# module_wifi.net
KiCad netlist of a schematic drawn in Altium Designer
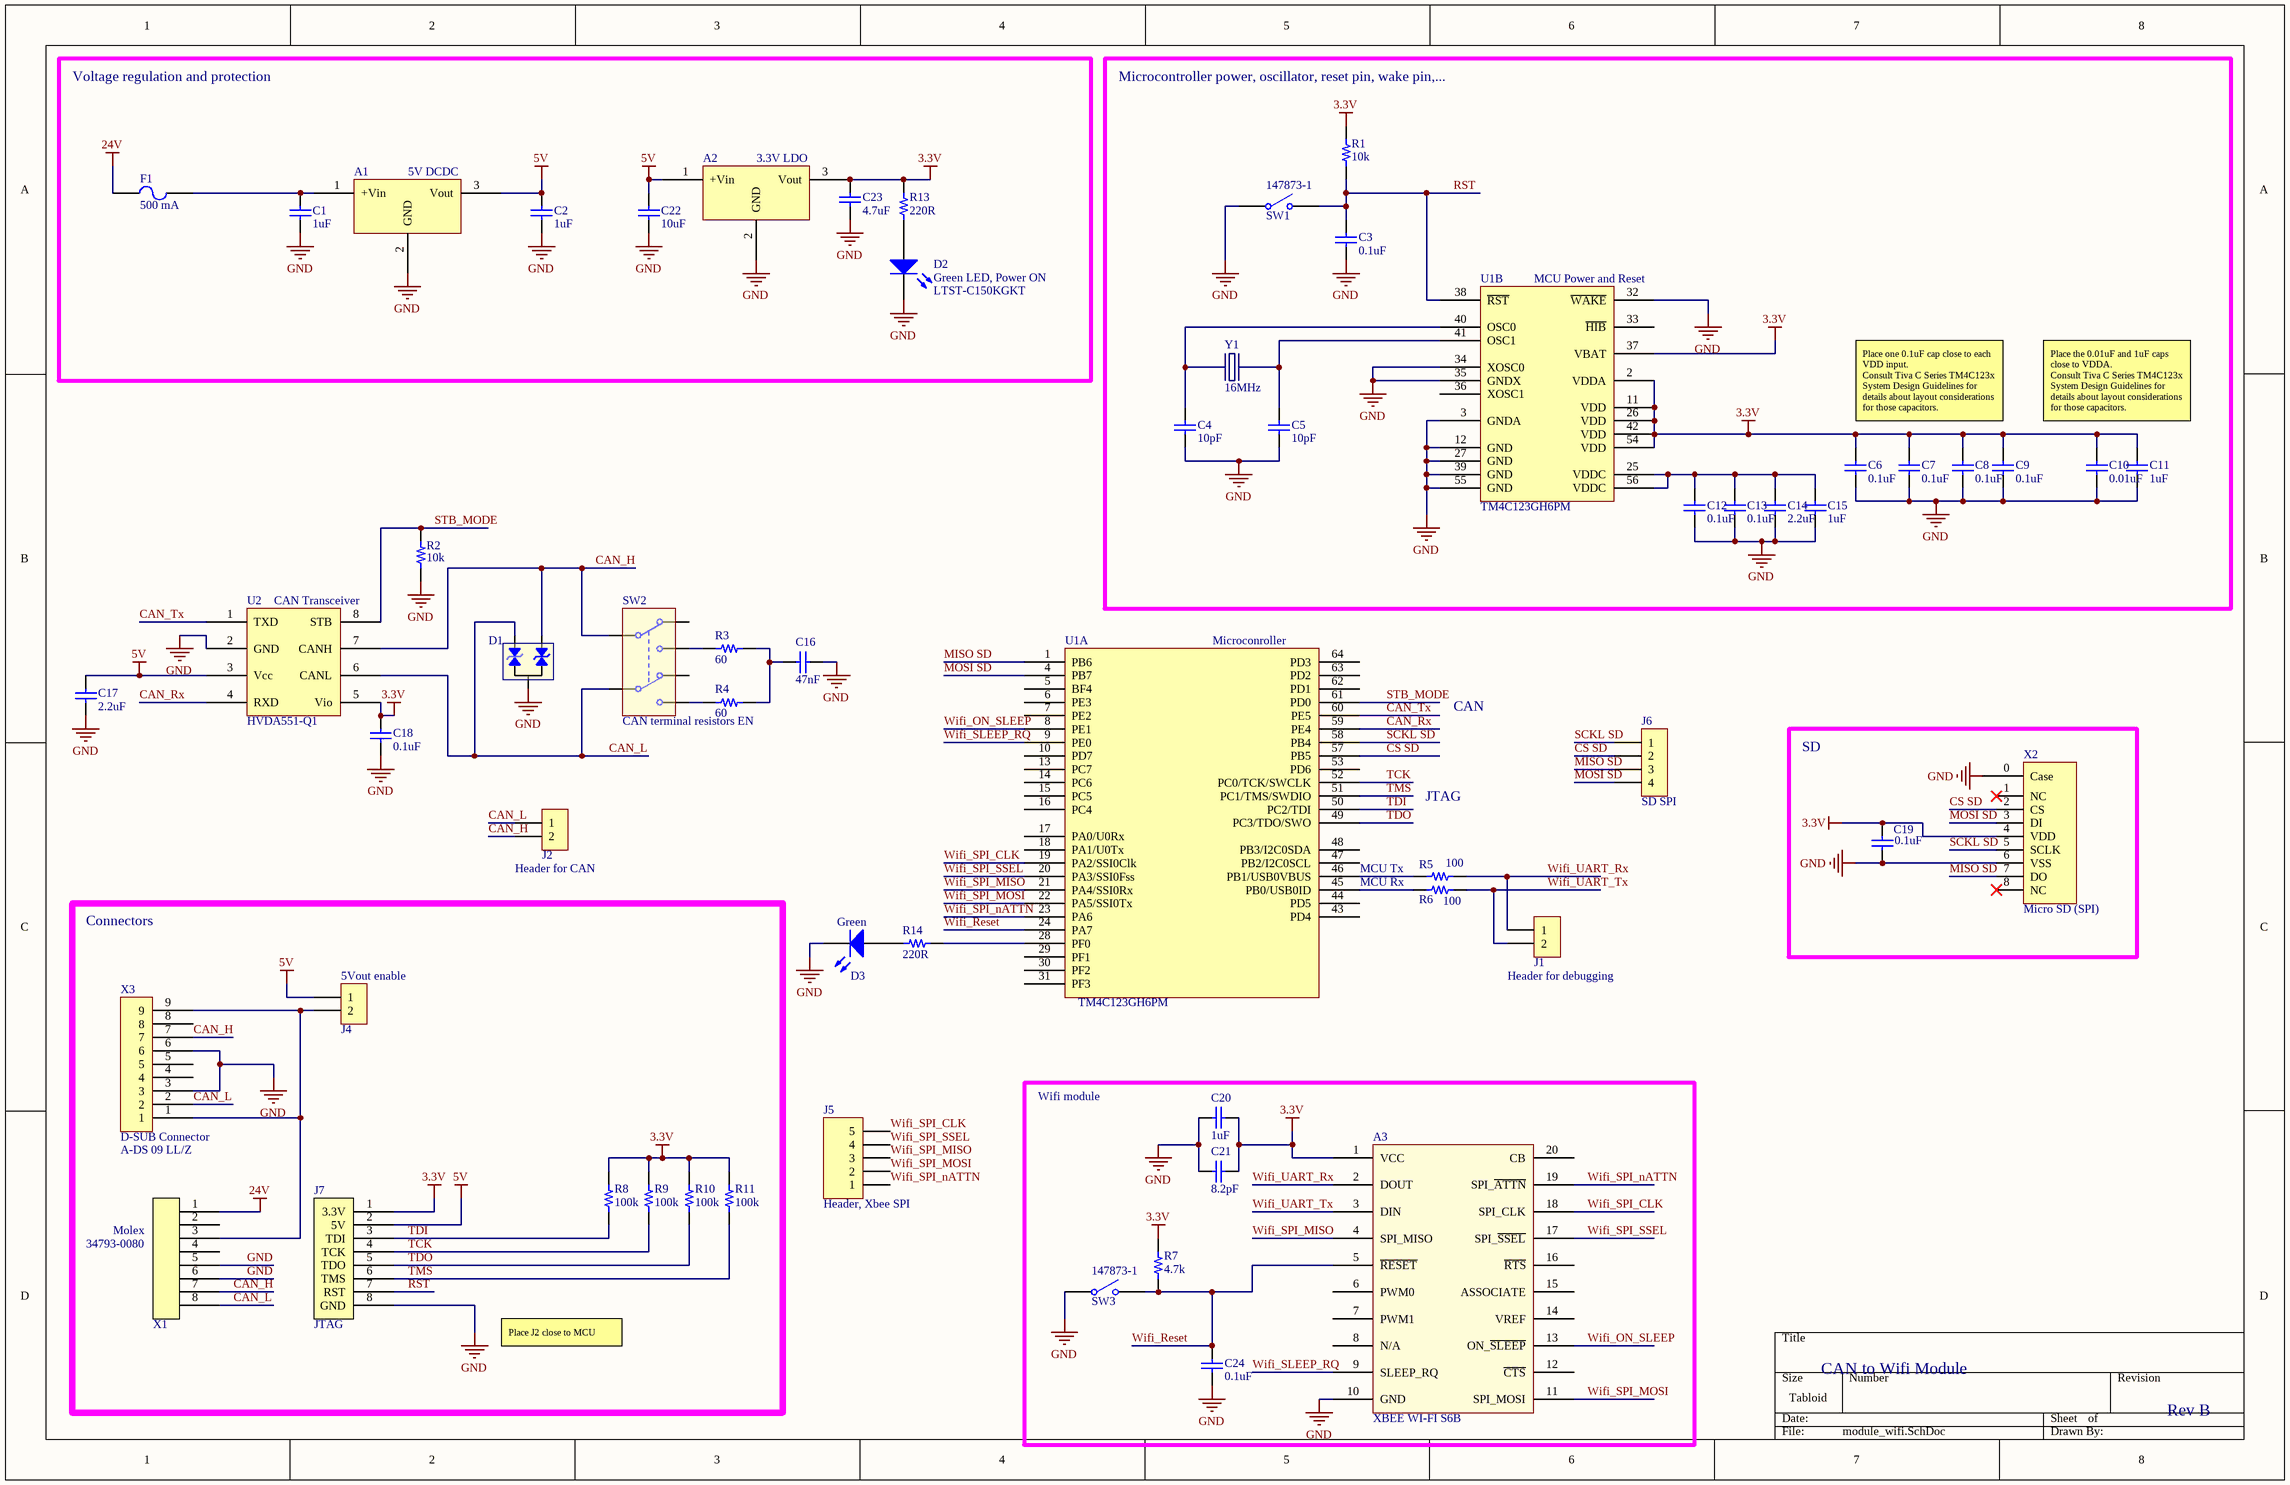
[diagram p0: module_wifi.SchDoc]

(export (version "E")
  (design (tool "Eeschema 10.0.6"))
  (components
    (comp (ref "A1")
      (value "5V DCDC")
      (footprint "R-78E-0.5")
      (fields (field (name "MANUFACTURER") "Recom") (field (name "PART_NUMBER") "R-78E5.0-0.5"))
      (libsource (lib "Other") (part "R78E5.0-0.5"))
    )
    (comp (ref "A2")
      (value "3.3V LDO")
      (footprint "TO252-3")
      (description "Linear Voltage Regulator IC Positive Fixed 1 Output 3.3V 500mA DPAK-3")
      (fields (field (name "MANUFACTURER") "ON Semiconductor") (field (name "PART_NUMBER") "NCV5501DT33RKG"))
      (libsource (lib "IC") (part "NCV5501DT33RKG"))
    )
    (comp (ref "A3")
      (value "XBEE WI-FI S6B")
      (footprint "Xbee_TH")
      (description "Module Wifi")
      (fields (field (name "MANUFACTURER") "Digi International") (field (name "PART_NUMBER") "XB2B-WFST-001"))
      (libsource (lib "Other") (part "XBEE WI-FI S6B"))
    )
    (comp (ref "C1")
      (value "1uF")
      (footprint "Capacitors:C0603")
      (description "1uF ceramic capacitor")
      (fields (field (name "MANUFACTURER") "TDK Corporation") (field (name "TOLERANCE") "20%"))
      (libsource (lib "Capacitors") (part "CAP CER 0603 1uF 25V X7R 20%"))
    )
    (comp (ref "C2")
      (value "1uF")
      (footprint "Capacitors:C0603")
      (description "1uF ceramic capacitor")
      (fields (field (name "MANUFACTURER") "TDK Corporation") (field (name "TOLERANCE") "20%"))
      (libsource (lib "Capacitors") (part "CAP CER 0603 1uF 25V X7R 20%"))
    )
    (comp (ref "C3")
      (value "0.1uF")
      (footprint "Capacitors:C0603")
      (description "0.1uF ceramic capacitor")
      (fields (field (name "MANUFACTURER") "TDK Corporation") (field (name "TOLERANCE") "10%"))
      (libsource (lib "Capacitors") (part "CAP CER 0603 0.1uF 50V C0G 10%"))
    )
    (comp (ref "C4")
      (value "10pF")
      (footprint "Capacitors:C0603")
      (description "10pF ceramic capacitor")
      (fields (field (name "MANUFACTURER") "TDK Corporation") (field (name "TOLERANCE") "5%"))
      (libsource (lib "Capacitors") (part "CAP CER 0603 10pF 50V C0G 5%"))
    )
    (comp (ref "C5")
      (value "10pF")
      (footprint "Capacitors:C0603")
      (description "10pF ceramic capacitor")
      (fields (field (name "MANUFACTURER") "TDK Corporation") (field (name "TOLERANCE") "5%"))
      (libsource (lib "Capacitors") (part "CAP CER 0603 10pF 50V C0G 5%"))
    )
    (comp (ref "C6")
      (value "0.1uF")
      (footprint "Capacitors:C0603")
      (description "0.1uF ceramic capacitor")
      (fields (field (name "MANUFACTURER") "TDK Corporation") (field (name "TOLERANCE") "10%"))
      (libsource (lib "Capacitors") (part "CAP CER 0603 0.1uF 50V C0G 10%"))
    )
    (comp (ref "C7")
      (value "0.1uF")
      (footprint "Capacitors:C0603")
      (description "0.1uF ceramic capacitor")
      (fields (field (name "MANUFACTURER") "TDK Corporation") (field (name "TOLERANCE") "10%"))
      (libsource (lib "Capacitors") (part "CAP CER 0603 0.1uF 50V C0G 10%"))
    )
    (comp (ref "C8")
      (value "0.1uF")
      (footprint "Capacitors:C0603")
      (description "0.1uF ceramic capacitor")
      (fields (field (name "MANUFACTURER") "TDK Corporation") (field (name "TOLERANCE") "10%"))
      (libsource (lib "Capacitors") (part "CAP CER 0603 0.1uF 50V C0G 10%"))
    )
    (comp (ref "C9")
      (value "0.1uF")
      (footprint "Capacitors:C0603")
      (description "0.1uF ceramic capacitor")
      (fields (field (name "MANUFACTURER") "TDK Corporation") (field (name "TOLERANCE") "10%"))
      (libsource (lib "Capacitors") (part "CAP CER 0603 0.1uF 50V C0G 10%"))
    )
    (comp (ref "C10")
      (value "0.01uF")
      (footprint "Capacitors:C0603")
      (description "0.01uF ceramic capacitor")
      (fields (field (name "MANUFACTURER") "TDK Corporation") (field (name "TOLERANCE") "10%"))
      (libsource (lib "Capacitors") (part "CAP CER 0603 0.01uF 50V X7R 10%"))
    )
    (comp (ref "C11")
      (value "1uF")
      (footprint "Capacitors:C0603")
      (description "1uF ceramic capacitor")
      (fields (field (name "MANUFACTURER") "TDK Corporation") (field (name "TOLERANCE") "20%"))
      (libsource (lib "Capacitors") (part "CAP CER 0603 1uF 25V X7R 20%"))
    )
    (comp (ref "C12")
      (value "0.1uF")
      (footprint "Capacitors:C0603")
      (description "0.1uF ceramic capacitor")
      (fields (field (name "MANUFACTURER") "TDK Corporation") (field (name "TOLERANCE") "10%"))
      (libsource (lib "Capacitors") (part "CAP CER 0603 0.1uF 50V C0G 10%"))
    )
    (comp (ref "C13")
      (value "0.1uF")
      (footprint "Capacitors:C0603")
      (description "0.1uF ceramic capacitor")
      (fields (field (name "MANUFACTURER") "TDK Corporation") (field (name "TOLERANCE") "10%"))
      (libsource (lib "Capacitors") (part "CAP CER 0603 0.1uF 50V C0G 10%"))
    )
    (comp (ref "C14")
      (value "2.2uF")
      (footprint "Capacitors:C0603")
      (description "2.2uF ceramic capacitor")
      (fields (field (name "MANUFACTURER") "TDK Corporation") (field (name "TOLERANCE") "10%"))
      (libsource (lib "Capacitors") (part "CAP CER 0603 2.2uF 6.3V X7R 10%"))
    )
    (comp (ref "C15")
      (value "1uF")
      (footprint "Capacitors:C0603")
      (description "1uF ceramic capacitor")
      (fields (field (name "MANUFACTURER") "TDK Corporation") (field (name "TOLERANCE") "20%"))
      (libsource (lib "Capacitors") (part "CAP CER 0603 1uF 25V X7R 20%"))
    )
    (comp (ref "C16")
      (value "47nF")
      (footprint "Capacitors:C0603")
      (description "47nF ceramic capacitor")
      (fields (field (name "MANUFACTURER") "TDK Corporation") (field (name "TOLERANCE") "10%"))
      (libsource (lib "Capacitors") (part "CAP CER 0603 47nF 50V X7R 10%"))
    )
    (comp (ref "C17")
      (value "2.2uF")
      (footprint "Capacitors:C0603")
      (description "2.2uF ceramic capacitor")
      (fields (field (name "MANUFACTURER") "TDK Corporation") (field (name "TOLERANCE") "10%"))
      (libsource (lib "Capacitors") (part "CAP CER 0603 2.2uF 6.3V X7R 10%"))
    )
    (comp (ref "C18")
      (value "0.1uF")
      (footprint "Capacitors:C0603")
      (description "0.1uF ceramic capacitor")
      (fields (field (name "MANUFACTURER") "TDK Corporation") (field (name "TOLERANCE") "10%"))
      (libsource (lib "Capacitors") (part "CAP CER 0603 0.1uF 50V C0G 10%"))
    )
    (comp (ref "C19")
      (value "0.1uF")
      (footprint "Capacitors:C0603")
      (description "0.1uF ceramic capacitor")
      (fields (field (name "MANUFACTURER") "TDK Corporation") (field (name "TOLERANCE") "10%"))
      (libsource (lib "Capacitors") (part "CAP CER 0603 0.1uF 50V C0G 10%"))
    )
    (comp (ref "C20")
      (value "1uF")
      (footprint "Capacitors:C0603")
      (description "1uF ceramic capacitor")
      (fields (field (name "MANUFACTURER") "TDK Corporation") (field (name "TOLERANCE") "20%"))
      (libsource (lib "Capacitors") (part "CAP CER 0603 1uF 25V X7R 20%"))
    )
    (comp (ref "C21")
      (value "8.2pF")
      (footprint "C0603")
      (description "8.2pF 50V Ceramic Capacitor C0G, NP0 0603")
      (fields
        (field (name "MANUFACTURER") "Murata-Electronics-North-America")
        (field (name "PART_NUMBER") "GCM1885C1H8R2DA16D")
      )
      (libsource (lib "Capacitors") (part "CAP CER 0603 8.2pF 50V COG ±0.5pF"))
    )
    (comp (ref "C22")
      (value "10uF")
      (footprint "Capacitors:C0603")
      (description "10uF ceramic capacitor")
      (fields (field (name "MANUFACTURER") "Taiyo Yuden") (field (name "TOLERANCE") "20%"))
      (libsource (lib "Capacitors") (part "CAP CER 0603 10uF 6.3V X5R 20%"))
    )
    (comp (ref "C23")
      (value "4.7uF")
      (footprint "Capacitors:C0603")
      (description "4.7uF ceramic capacitor")
      (fields (field (name "MANUFACTURER") "Kernet") (field (name "TOLERANCE") "10%"))
      (libsource (lib "Capacitors") (part "CAP CER 0603 4.7uF 25V X7R 10%"))
    )
    (comp (ref "C24")
      (value "0.1uF")
      (footprint "Capacitors:C0603")
      (description "0.1uF ceramic capacitor")
      (fields (field (name "MANUFACTURER") "TDK Corporation") (field (name "TOLERANCE") "10%"))
      (libsource (lib "Capacitors") (part "CAP CER 0603 0.1uF 50V C0G 10%"))
    )
    (comp (ref "D1")
      (value "PESD1CAN-UX")
      (footprint "SOT23")
      (description "TVS diodes for CAN bus")
      (fields (field (name "MANUFACTURER") "NXP"))
      (libsource (lib "Diodes") (part "PESD1CAN-UX"))
    )
    (comp (ref "D2")
      (value "Green LED, Power ON")
      (footprint "LED1206")
      (description "Green LED 1206")
      (fields (field (name "MANUFACTURER") "Liteon") (field (name "PART_NUMBER") "LTST-C150KGKT"))
      (libsource (lib "Diodes") (part "LTST-C150KGKT"))
    )
    (comp (ref "D3")
      (value "Green")
      (footprint "Diodes:LED1206")
      (description "Green LED 1206")
      (fields (field (name "PART_NUMBER") "LTST-C150KGKT") (field (name "MANUFACTURER") "Liteon"))
      (libsource (lib "Diodes") (part "LTST-C150KGKT"))
    )
    (comp (ref "F1")
      (value "500 mA")
      (footprint "R0603")
      (description "Fuse, 500 mA, 63VDC, 0603, fast")
      (fields (field (name "PART_NUMBER") "C2Q 500") (field (name "MANUFACTURER") "Bel Fuse"))
      (libsource (lib "Fuses") (part "C2Q500"))
    )
    (comp (ref "J1")
      (value "Header for debugging")
      (footprint "HDR1X2")
      (description "Header, 2-Pin")
      (libsource (lib "Connectors") (part "Header 2"))
    )
    (comp (ref "J2")
      (value "Header for CAN")
      (footprint "HDR1X2")
      (description "Header, 2-Pin")
      (libsource (lib "Connectors") (part "Header 2"))
    )
    (comp (ref "J4")
      (value "5Vout enable")
      (footprint "HDR1X2")
      (description "Header, 2-Pin")
      (libsource (lib "Connectors") (part "Header 2"))
    )
    (comp (ref "J5")
      (value "Header, Xbee SPI")
      (footprint "Connectors:HDR1X5")
      (description "Header, 5-Pin")
      (libsource (lib "Connectors") (part "Header 5"))
    )
    (comp (ref "J6")
      (value "SD SPI")
      (footprint "Connectors:HDR1X4")
      (description "Header, 4-Pin")
      (libsource (lib "Connectors") (part "Header 4"))
    )
    (comp (ref "J7")
      (value "JTAG")
      (footprint "Connectors:JTAG_Header")
      (description "JTAG header, MCU programming")
      (libsource (lib "Connectors") (part "JTAG_Header"))
    )
    (comp (ref "R1")
      (value "10k")
      (footprint "Resistors:R0603")
      (description "10 kOhms resistor")
      (fields (field (name "PART_NUMBER") "CRCW060310K0JNEA") (field (name "MANUFACTURER") "Vishay"))
      (libsource (lib "Resistors") (part "RES 0603 10k 5% 0.1W"))
    )
    (comp (ref "R2")
      (value "10k")
      (footprint "Resistors:R0603")
      (description "10 kOhms resistor")
      (fields (field (name "PART_NUMBER") "CRCW060310K0JNEA") (field (name "MANUFACTURER") "Vishay"))
      (libsource (lib "Resistors") (part "RES 0603 10k 5% 0.1W"))
    )
    (comp (ref "R3")
      (value "60")
      (footprint "Resistors:R0603")
      (description "60 Ohms resistor, 1/4W")
      (fields (field (name "PART_NUMBER") "ESR03EZPJ620") (field (name "MANUFACTURER") "Rohm Semiconductor"))
      (libsource (lib "Resistors") (part "RES 0603 60R 1% 1/4W"))
    )
    (comp (ref "R4")
      (value "60")
      (footprint "Resistors:R0603")
      (description "60 Ohms resistor, 1/4W")
      (fields (field (name "PART_NUMBER") "ESR03EZPJ620") (field (name "MANUFACTURER") "Rohm Semiconductor"))
      (libsource (lib "Resistors") (part "RES 0603 60R 1% 1/4W"))
    )
    (comp (ref "R5")
      (value "100")
      (footprint "Resistors:R0603")
      (description "100 Ohms resistor, 1/4W")
      (fields (field (name "PART_NUMBER") "ESR03EZPJ101") (field (name "MANUFACTURER") "Rohm Semiconductor"))
      (libsource (lib "Resistors") (part "RES 0603 100R 5% 1/4W"))
    )
    (comp (ref "R6")
      (value "100")
      (footprint "Resistors:R0603")
      (description "100 Ohms resistor, 1/4W")
      (fields (field (name "PART_NUMBER") "ESR03EZPJ101") (field (name "MANUFACTURER") "Rohm Semiconductor"))
      (libsource (lib "Resistors") (part "RES 0603 100R 5% 1/4W"))
    )
    (comp (ref "R7")
      (value "4.7k")
      (footprint "Resistors:R0603")
      (description "4.7 kOhms resistor")
      (fields (field (name "PART_NUMBER") "CRCW06034K70JNEA") (field (name "MANUFACTURER") "Vishay"))
      (libsource (lib "Resistors") (part "RES 0603 4.7k 5% 0.1W"))
    )
    (comp (ref "R8")
      (value "100k")
      (footprint "Resistors:R0603")
      (description "100 kOhm resistor")
      (fields (field (name "PART_NUMBER") "CRCW0603100KJNEA") (field (name "MANUFACTURER") "Vishay"))
      (libsource (lib "Resistors") (part "RES 0603 100k 5% 0.1W"))
    )
    (comp (ref "R9")
      (value "100k")
      (footprint "Resistors:R0603")
      (description "100 kOhm resistor")
      (fields (field (name "PART_NUMBER") "CRCW0603100KJNEA") (field (name "MANUFACTURER") "Vishay"))
      (libsource (lib "Resistors") (part "RES 0603 100k 5% 0.1W"))
    )
    (comp (ref "R10")
      (value "100k")
      (footprint "Resistors:R0603")
      (description "100 kOhm resistor")
      (fields (field (name "PART_NUMBER") "CRCW0603100KJNEA") (field (name "MANUFACTURER") "Vishay"))
      (libsource (lib "Resistors") (part "RES 0603 100k 5% 0.1W"))
    )
    (comp (ref "R11")
      (value "100k")
      (footprint "Resistors:R0603")
      (description "100 kOhm resistor")
      (fields (field (name "PART_NUMBER") "CRCW0603100KJNEA") (field (name "MANUFACTURER") "Vishay"))
      (libsource (lib "Resistors") (part "RES 0603 100k 5% 0.1W"))
    )
    (comp (ref "R13")
      (value "220R")
      (footprint "R0603")
      (description "220 Ohms 0.25W Resistor")
      (fields (field (name "PART_NUMBER") "ESR03EZPJ221") (field (name "MANUFACTURER") "Rohm Semiconductor"))
      (libsource (lib "Resistors") (part "RES 0603 220R 5% 0.25W"))
    )
    (comp (ref "R14")
      (value "220R")
      (footprint "Resistors:R0603")
      (description "220 Ohms resistor, 1/4W")
      (fields (field (name "PART_NUMBER") "ESR03EZPJ221") (field (name "MANUFACTURER") "Rohm Semiconductor"))
      (libsource (lib "Resistors") (part "RES 0603 220R 5% 1/4W"))
    )
    (comp (ref "SW1")
      (value "147873-1")
      (footprint "Other:147873")
      (description "Pushbutton switch SPST, 2 pins")
      (fields (field (name "MANUFACTURER") "TE Connectivity"))
      (libsource (lib "Other") (part "147873-1"))
    )
    (comp (ref "SW2")
      (value "CAN terminal resistors EN")
      (footprint "CL-SB-22A-01T")
      (description "SWITCH SLIDE DPDT 200MA 12VDC")
      (fields
        (field (name "MANUFACTURER") "Copal Electronics Inc.")
        (field (name "PART_NUMBER") "CL-SB-22A-01T")
      )
      (libsource (lib "Other") (part "CL-SB-22A-01T"))
    )
    (comp (ref "SW3")
      (value "147873-1")
      (footprint "Other:147873")
      (description "Pushbutton switch SPST, 2 pins")
      (fields (field (name "MANUFACTURER") "TE Connectivity"))
      (libsource (lib "Other") (part "147873-1"))
    )
    (comp (ref "U1")
      (value "Microconroller")
      (footprint "IC:LQFP64")
      (description "32 bit Microcontroller")
      (fields (field (name "MANUFACTURER") "Texas Instrument") (field (name "PART_NUMBER") "TM4C123GH6PM"))
      (libsource (lib "IC") (part "TM4C123GN6PM"))
    )
    (comp (ref "U2")
      (value "CAN Transceiver")
      (footprint "SOIC-8")
      (description "Automotive 5-V CAN Transceiver with I/O Level Adapting and Low-Power Mode Supply Optimization")
      (fields (field (name "MANUFACTURER") "Texas Instrument") (field (name "PART_NUMBER") "HVDA551-Q1"))
      (libsource (lib "IC") (part "HVDA551-Q1"))
    )
    (comp (ref "X1")
      (value "34793-0080")
      (footprint "Connectors:34791-0080")
      (description "Molex Mini50, 8 position, single row, right angle")
      (fields (field (name "MANUFACTURER") "Molex") (field (name "PART_NUMBER") "34793-0080"))
      (libsource (lib "Connectors") (part "34793-0080"))
    )
    (comp (ref "X2")
      (value "Micro SD (SPI)")
      (footprint "475710001")
      (description "microSD connector, Surface Mount, Right Angle")
      (fields (field (name "MANUFACTURER") "Molex") (field (name "PART_NUMBER") "47571-0001"))
      (libsource (lib "Other") (part "475710001"))
    )
    (comp (ref "X3")
      (value "D-SUB Connector")
      (footprint "A-DS 09 LL/Z")
      (description "CONN D-SUB PLUG 9POS R/A SOLDER")
      (fields
        (field (name "MANUFACTURER") "Assmann WSW Components")
        (field (name "PART_NUMBER") "A-DS 09 LL/Z")
      )
      (libsource (lib "Connectors") (part "A-DS 09 LL/Z"))
    )
    (comp (ref "Y1")
      (value "16MHz")
      (footprint "NX5032GA")
      (description "Crystal Oscillator 16 MHz")
      (fields (field (name "MANUFACTURER") "NDK") (field (name "PART_NUMBER") "NX5032GA-16.000M-LN-CD-1"))
      (libsource (lib "Other") (part "NX5043GA-16.00MHz"))
    )
  )
  (nets
    (net (code "1") (name "/CAN_H") (class "Default")
      (node (ref "D1") (pin "1") (pinfunction "1_1") (pintype "passive"))
      (node (ref "J2") (pin "2") (pinfunction "2_2") (pintype "passive"))
      (node (ref "SW2") (pin "2") (pinfunction "COMMON1_2") (pintype "passive"))
      (node (ref "U2") (pin "7") (pinfunction "CANH_7") (pintype "passive"))
      (node (ref "X1") (pin "7") (pinfunction "7_7") (pintype "passive"))
      (node (ref "X3") (pin "7") (pinfunction "7_7") (pintype "passive"))
    )
    (net (code "2") (name "/CAN_L") (class "Default")
      (node (ref "D1") (pin "2") (pinfunction "2_2") (pintype "passive"))
      (node (ref "J2") (pin "1") (pinfunction "1_1") (pintype "passive"))
      (node (ref "SW2") (pin "5") (pinfunction "COMMON2_5") (pintype "passive"))
      (node (ref "U2") (pin "6") (pinfunction "CANL_6") (pintype "passive"))
      (node (ref "X1") (pin "8") (pinfunction "8_8") (pintype "passive"))
      (node (ref "X3") (pin "2") (pinfunction "2_2") (pintype "passive"))
    )
    (net (code "3") (name "/CAN_Rx") (class "Default")
      (node (ref "U1") (pin "59") (pinfunction "PE4_59") (pintype "passive"))
      (node (ref "U2") (pin "4") (pinfunction "RXD_4") (pintype "passive"))
    )
    (net (code "4") (name "/CAN_Tx") (class "Default")
      (node (ref "U1") (pin "60") (pinfunction "PE5_60") (pintype "passive"))
      (node (ref "U2") (pin "1") (pinfunction "TXD_1") (pintype "passive"))
    )
    (net (code "5") (name "/CS SD") (class "Default")
      (node (ref "J6") (pin "2") (pinfunction "2_2") (pintype "passive"))
      (node (ref "U1") (pin "57") (pinfunction "PB5_57") (pintype "passive"))
      (node (ref "X2") (pin "2") (pinfunction "CS_2") (pintype "passive"))
    )
    (net (code "6") (name "/MISO SD") (class "Default")
      (node (ref "J6") (pin "3") (pinfunction "3_3") (pintype "passive"))
      (node (ref "U1") (pin "1") (pinfunction "PB6_1") (pintype "passive"))
      (node (ref "X2") (pin "7") (pinfunction "DO_7") (pintype "passive"))
    )
    (net (code "7") (name "/MOSI SD") (class "Default")
      (node (ref "J6") (pin "4") (pinfunction "4_4") (pintype "passive"))
      (node (ref "U1") (pin "4") (pinfunction "PB7_4") (pintype "passive"))
      (node (ref "X2") (pin "3") (pinfunction "DI_3") (pintype "passive"))
    )
    (net (code "8") (name "/RST") (class "Default")
      (node (ref "C3") (pin "2") (pinfunction "2_2") (pintype "passive"))
      (node (ref "J7") (pin "7") (pinfunction "RST_7") (pintype "passive"))
      (node (ref "R1") (pin "1") (pinfunction "1_1") (pintype "passive"))
      (node (ref "SW1") (pin "2") (pinfunction "NO_2") (pintype "passive"))
      (node (ref "U1") (pin "38") (pinfunction "~{RST}_38") (pintype "passive"))
    )
    (net (code "9") (name "/SCKL SD") (class "Default")
      (node (ref "J6") (pin "1") (pinfunction "1_1") (pintype "passive"))
      (node (ref "U1") (pin "58") (pinfunction "PB4_58") (pintype "passive"))
      (node (ref "X2") (pin "5") (pinfunction "SCLK_5") (pintype "passive"))
    )
    (net (code "10") (name "/STB_MODE") (class "Default")
      (node (ref "R2") (pin "2") (pinfunction "2_2") (pintype "passive"))
      (node (ref "U1") (pin "61") (pinfunction "PD0_61") (pintype "passive"))
      (node (ref "U2") (pin "8") (pinfunction "STB_8") (pintype "passive"))
    )
    (net (code "11") (name "/TCK") (class "Default")
      (node (ref "J7") (pin "4") (pinfunction "TCK_4") (pintype "passive"))
      (node (ref "R9") (pin "1") (pinfunction "1_1") (pintype "passive"))
      (node (ref "U1") (pin "52") (pinfunction "PC0/TCK/SWCLK_52") (pintype "passive"))
    )
    (net (code "12") (name "/TDI") (class "Default")
      (node (ref "J7") (pin "3") (pinfunction "TDI_3") (pintype "passive"))
      (node (ref "R8") (pin "1") (pinfunction "1_1") (pintype "passive"))
      (node (ref "U1") (pin "50") (pinfunction "PC2/TDI_50") (pintype "passive"))
    )
    (net (code "13") (name "/TDO") (class "Default")
      (node (ref "J7") (pin "5") (pinfunction "TDO_5") (pintype "passive"))
      (node (ref "R10") (pin "1") (pinfunction "1_1") (pintype "passive"))
      (node (ref "U1") (pin "49") (pinfunction "PC3/TDO/SWO_49") (pintype "passive"))
    )
    (net (code "14") (name "/TMS") (class "Default")
      (node (ref "J7") (pin "6") (pinfunction "TMS_6") (pintype "passive"))
      (node (ref "R11") (pin "1") (pinfunction "1_1") (pintype "passive"))
      (node (ref "U1") (pin "51") (pinfunction "PC1/TMS/SWDIO_51") (pintype "passive"))
    )
    (net (code "15") (name "/Wifi_ON_SLEEP") (class "Default")
      (node (ref "A3") (pin "13") (pinfunction "ON_~{SLEEP}_13") (pintype "passive"))
      (node (ref "U1") (pin "8") (pinfunction "PE1_8") (pintype "passive"))
    )
    (net (code "16") (name "/Wifi_Reset") (class "Default")
      (node (ref "A3") (pin "5") (pinfunction "~{RESET}_5") (pintype "passive"))
      (node (ref "C24") (pin "2") (pinfunction "2_2") (pintype "passive"))
      (node (ref "R7") (pin "1") (pinfunction "1_1") (pintype "passive"))
      (node (ref "SW3") (pin "2") (pinfunction "NO_2") (pintype "passive"))
      (node (ref "U1") (pin "24") (pinfunction "PA7_24") (pintype "passive"))
    )
    (net (code "17") (name "/Wifi_SLEEP_RQ") (class "Default")
      (node (ref "A3") (pin "9") (pinfunction "SLEEP_RQ_9") (pintype "passive"))
      (node (ref "U1") (pin "9") (pinfunction "PE0_9") (pintype "passive"))
    )
    (net (code "18") (name "/Wifi_SPI_CLK") (class "Default")
      (node (ref "A3") (pin "18") (pinfunction "SPI_CLK_18") (pintype "passive"))
      (node (ref "J5") (pin "5") (pinfunction "5_5") (pintype "passive"))
      (node (ref "U1") (pin "19") (pinfunction "PA2/SSI0Clk_19") (pintype "passive"))
    )
    (net (code "19") (name "/Wifi_SPI_MISO") (class "Default")
      (node (ref "A3") (pin "4") (pinfunction "SPI_MISO_4") (pintype "passive"))
      (node (ref "J5") (pin "3") (pinfunction "3_3") (pintype "passive"))
      (node (ref "U1") (pin "21") (pinfunction "PA4/SSI0Rx_21") (pintype "passive"))
    )
    (net (code "20") (name "/Wifi_SPI_MOSI") (class "Default")
      (node (ref "A3") (pin "11") (pinfunction "SPI_MOSI_11") (pintype "passive"))
      (node (ref "J5") (pin "2") (pinfunction "2_2") (pintype "passive"))
      (node (ref "U1") (pin "22") (pinfunction "PA5/SSI0Tx_22") (pintype "passive"))
    )
    (net (code "21") (name "/Wifi_SPI_SSEL") (class "Default")
      (node (ref "A3") (pin "17") (pinfunction "SPI_~{SSEL}_17") (pintype "passive"))
      (node (ref "J5") (pin "4") (pinfunction "4_4") (pintype "passive"))
      (node (ref "U1") (pin "20") (pinfunction "PA3/SSI0Fss_20") (pintype "passive"))
    )
    (net (code "22") (name "/Wifi_SPI_nATTN") (class "Default")
      (node (ref "A3") (pin "19") (pinfunction "SPI_~{ATTN}_19") (pintype "passive"))
      (node (ref "J5") (pin "1") (pinfunction "1_1") (pintype "passive"))
      (node (ref "U1") (pin "23") (pinfunction "PA6_23") (pintype "passive"))
    )
    (net (code "23") (name "/Wifi_UART_Rx") (class "Default")
      (node (ref "A3") (pin "2") (pinfunction "DOUT_2") (pintype "passive"))
      (node (ref "J1") (pin "1") (pinfunction "1_1") (pintype "passive"))
      (node (ref "R5") (pin "1") (pinfunction "1_1") (pintype "passive"))
    )
    (net (code "24") (name "/Wifi_UART_Tx") (class "Default")
      (node (ref "A3") (pin "3") (pinfunction "DIN_3") (pintype "passive"))
      (node (ref "J1") (pin "2") (pinfunction "2_2") (pintype "passive"))
      (node (ref "R6") (pin "1") (pinfunction "1_1") (pintype "passive"))
    )
    (net (code "25") (name "3.3V") (class "Default")
      (node (ref "A2") (pin "3") (pinfunction "Vout_3") (pintype "passive"))
      (node (ref "A3") (pin "1") (pinfunction "VCC_1") (pintype "passive"))
      (node (ref "C10") (pin "2") (pinfunction "2_2") (pintype "passive"))
      (node (ref "C11") (pin "2") (pinfunction "2_2") (pintype "passive"))
      (node (ref "C18") (pin "2") (pinfunction "2_2") (pintype "passive"))
      (node (ref "C19") (pin "2") (pinfunction "2_2") (pintype "passive"))
      (node (ref "C20") (pin "2") (pinfunction "2_2") (pintype "passive"))
      (node (ref "C21") (pin "2") (pinfunction "2_2") (pintype "passive"))
      (node (ref "C23") (pin "2") (pinfunction "2_2") (pintype "passive"))
      (node (ref "C6") (pin "2") (pinfunction "2_2") (pintype "passive"))
      (node (ref "C7") (pin "2") (pinfunction "2_2") (pintype "passive"))
      (node (ref "C8") (pin "2") (pinfunction "2_2") (pintype "passive"))
      (node (ref "C9") (pin "2") (pinfunction "2_2") (pintype "passive"))
      (node (ref "J7") (pin "1") (pinfunction "3.3V_1") (pintype "passive"))
      (node (ref "R1") (pin "2") (pinfunction "2_2") (pintype "passive"))
      (node (ref "R10") (pin "2") (pinfunction "2_2") (pintype "passive"))
      (node (ref "R11") (pin "2") (pinfunction "2_2") (pintype "passive"))
      (node (ref "R13") (pin "2") (pinfunction "2_2") (pintype "passive"))
      (node (ref "R7") (pin "2") (pinfunction "2_2") (pintype "passive"))
      (node (ref "R8") (pin "2") (pinfunction "2_2") (pintype "passive"))
      (node (ref "R9") (pin "2") (pinfunction "2_2") (pintype "passive"))
      (node (ref "U1") (pin "11") (pinfunction "VDD_11") (pintype "passive"))
      (node (ref "U1") (pin "2") (pinfunction "VDDA_2") (pintype "passive"))
      (node (ref "U1") (pin "26") (pinfunction "VDD_26") (pintype "passive"))
      (node (ref "U1") (pin "37") (pinfunction "VBAT_37") (pintype "passive"))
      (node (ref "U1") (pin "42") (pinfunction "VDD_42") (pintype "passive"))
      (node (ref "U1") (pin "54") (pinfunction "VDD_54") (pintype "passive"))
      (node (ref "U2") (pin "5") (pinfunction "Vio_5") (pintype "passive"))
      (node (ref "X2") (pin "4") (pinfunction "VDD_4") (pintype "passive"))
    )
    (net (code "26") (name "5V") (class "Default")
      (node (ref "A1") (pin "3") (pinfunction "Vout_3") (pintype "passive"))
      (node (ref "A2") (pin "1") (pinfunction "+Vin_1") (pintype "passive"))
      (node (ref "C17") (pin "2") (pinfunction "2_2") (pintype "passive"))
      (node (ref "C2") (pin "2") (pinfunction "2_2") (pintype "passive"))
      (node (ref "C22") (pin "2") (pinfunction "2_2") (pintype "passive"))
      (node (ref "J4") (pin "1") (pinfunction "1_1") (pintype "passive"))
      (node (ref "J7") (pin "2") (pinfunction "5V_2") (pintype "passive"))
      (node (ref "U2") (pin "3") (pinfunction "Vcc_3") (pintype "power_in"))
    )
    (net (code "27") (name "24V") (class "Default")
      (node (ref "F1") (pin "2") (pinfunction "2_2") (pintype "passive"))
      (node (ref "X1") (pin "1") (pinfunction "1_1") (pintype "passive"))
    )
    (net (code "28") (name "GND") (class "Default")
      (node (ref "A1") (pin "2") (pinfunction "GND_2") (pintype "passive"))
      (node (ref "A2") (pin "2") (pinfunction "GND_2") (pintype "passive"))
      (node (ref "A3") (pin "10") (pinfunction "GND_10") (pintype "passive"))
      (node (ref "C1") (pin "1") (pinfunction "1_1") (pintype "passive"))
      (node (ref "C10") (pin "1") (pinfunction "1_1") (pintype "passive"))
      (node (ref "C11") (pin "1") (pinfunction "1_1") (pintype "passive"))
      (node (ref "C12") (pin "1") (pinfunction "1_1") (pintype "passive"))
      (node (ref "C13") (pin "1") (pinfunction "1_1") (pintype "passive"))
      (node (ref "C14") (pin "1") (pinfunction "1_1") (pintype "passive"))
      (node (ref "C15") (pin "1") (pinfunction "1_1") (pintype "passive"))
      (node (ref "C16") (pin "2") (pinfunction "2_2") (pintype "passive"))
      (node (ref "C17") (pin "1") (pinfunction "1_1") (pintype "passive"))
      (node (ref "C18") (pin "1") (pinfunction "1_1") (pintype "passive"))
      (node (ref "C19") (pin "1") (pinfunction "1_1") (pintype "passive"))
      (node (ref "C2") (pin "1") (pinfunction "1_1") (pintype "passive"))
      (node (ref "C20") (pin "1") (pinfunction "1_1") (pintype "passive"))
      (node (ref "C21") (pin "1") (pinfunction "1_1") (pintype "passive"))
      (node (ref "C22") (pin "1") (pinfunction "1_1") (pintype "passive"))
      (node (ref "C23") (pin "1") (pinfunction "1_1") (pintype "passive"))
      (node (ref "C24") (pin "1") (pinfunction "1_1") (pintype "passive"))
      (node (ref "C3") (pin "1") (pinfunction "1_1") (pintype "passive"))
      (node (ref "C4") (pin "1") (pinfunction "1_1") (pintype "passive"))
      (node (ref "C5") (pin "1") (pinfunction "1_1") (pintype "passive"))
      (node (ref "C6") (pin "1") (pinfunction "1_1") (pintype "passive"))
      (node (ref "C7") (pin "1") (pinfunction "1_1") (pintype "passive"))
      (node (ref "C8") (pin "1") (pinfunction "1_1") (pintype "passive"))
      (node (ref "C9") (pin "1") (pinfunction "1_1") (pintype "passive"))
      (node (ref "D1") (pin "3") (pinfunction "3_3") (pintype "passive"))
      (node (ref "D2") (pin "2") (pinfunction "K_2") (pintype "passive"))
      (node (ref "D3") (pin "2") (pinfunction "K_2") (pintype "passive"))
      (node (ref "J7") (pin "8") (pinfunction "GND_8") (pintype "passive"))
      (node (ref "R2") (pin "1") (pinfunction "1_1") (pintype "passive"))
      (node (ref "SW1") (pin "1") (pinfunction "COMMON_1") (pintype "passive"))
      (node (ref "SW3") (pin "1") (pinfunction "COMMON_1") (pintype "passive"))
      (node (ref "U1") (pin "12") (pinfunction "GND_12") (pintype "passive"))
      (node (ref "U1") (pin "27") (pinfunction "GND_27") (pintype "passive"))
      (node (ref "U1") (pin "3") (pinfunction "GNDA_3") (pintype "passive"))
      (node (ref "U1") (pin "32") (pinfunction "~{WAKE}_32") (pintype "passive"))
      (node (ref "U1") (pin "34") (pinfunction "XOSC0_34") (pintype "passive"))
      (node (ref "U1") (pin "35") (pinfunction "GNDX_35") (pintype "passive"))
      (node (ref "U1") (pin "39") (pinfunction "GND_39") (pintype "passive"))
      (node (ref "U1") (pin "55") (pinfunction "GND_55") (pintype "passive"))
      (node (ref "U2") (pin "2") (pinfunction "GND_2") (pintype "power_in"))
      (node (ref "X1") (pin "5") (pinfunction "5_5") (pintype "passive"))
      (node (ref "X1") (pin "6") (pinfunction "6_6") (pintype "passive"))
      (node (ref "X2") (pin "0") (pinfunction "Case_0") (pintype "passive"))
      (node (ref "X2") (pin "6") (pinfunction "VSS_6") (pintype "passive"))
      (node (ref "X3") (pin "3") (pinfunction "3_3") (pintype "passive"))
      (node (ref "X3") (pin "6") (pinfunction "6_6") (pintype "passive"))
    )
    (net (code "29") (name "Net-(A1-+Vin)") (class "Default")
      (node (ref "A1") (pin "1") (pinfunction "+Vin_1") (pintype "passive"))
      (node (ref "C1") (pin "2") (pinfunction "2_2") (pintype "passive"))
      (node (ref "F1") (pin "1") (pinfunction "1_1") (pintype "passive"))
    )
    (net (code "30") (name "Net-(C12-Pad2)") (class "Default")
      (node (ref "C12") (pin "2") (pinfunction "2_2") (pintype "passive"))
      (node (ref "C13") (pin "2") (pinfunction "2_2") (pintype "passive"))
      (node (ref "C14") (pin "2") (pinfunction "2_2") (pintype "passive"))
      (node (ref "C15") (pin "2") (pinfunction "2_2") (pintype "passive"))
      (node (ref "U1") (pin "25") (pinfunction "VDDC_25") (pintype "passive"))
      (node (ref "U1") (pin "56") (pinfunction "VDDC_56") (pintype "passive"))
    )
    (net (code "31") (name "Net-(C16-Pad1)") (class "Default")
      (node (ref "C16") (pin "1") (pinfunction "1_1") (pintype "passive"))
      (node (ref "R3") (pin "1") (pinfunction "1_1") (pintype "passive"))
      (node (ref "R4") (pin "1") (pinfunction "1_1") (pintype "passive"))
    )
    (net (code "32") (name "Net-(D2-A)") (class "Default")
      (node (ref "D2") (pin "1") (pinfunction "A_1") (pintype "passive"))
      (node (ref "R13") (pin "1") (pinfunction "1_1") (pintype "passive"))
    )
    (net (code "33") (name "Net-(D3-A)") (class "Default")
      (node (ref "D3") (pin "1") (pinfunction "A_1") (pintype "passive"))
      (node (ref "R14") (pin "1") (pinfunction "1_1") (pintype "passive"))
    )
    (net (code "34") (name "Net-(J4-Pad2)") (class "Default")
      (node (ref "J4") (pin "2") (pinfunction "2_2") (pintype "passive"))
      (node (ref "X1") (pin "3") (pinfunction "3_3") (pintype "passive"))
      (node (ref "X3") (pin "1") (pinfunction "1_1") (pintype "passive"))
      (node (ref "X3") (pin "9") (pinfunction "9_9") (pintype "passive"))
    )
    (net (code "35") (name "Net-(SW2-NO1)") (class "Default")
      (node (ref "R3") (pin "2") (pinfunction "2_2") (pintype "passive"))
      (node (ref "SW2") (pin "3") (pinfunction "NO1_3") (pintype "passive"))
    )
    (net (code "36") (name "Net-(SW2-NO2)") (class "Default")
      (node (ref "R4") (pin "2") (pinfunction "2_2") (pintype "passive"))
      (node (ref "SW2") (pin "6") (pinfunction "NO2_6") (pintype "passive"))
    )
    (net (code "37") (name "Net-(U1A-PB0{slash}USB0ID)") (class "Default")
      (node (ref "R6") (pin "2") (pinfunction "2_2") (pintype "passive"))
      (node (ref "U1") (pin "45") (pinfunction "PB0/USB0ID_45") (pintype "passive"))
    )
    (net (code "38") (name "Net-(U1A-PB1{slash}USB0VBUS)") (class "Default")
      (node (ref "R5") (pin "2") (pinfunction "2_2") (pintype "passive"))
      (node (ref "U1") (pin "46") (pinfunction "PB1/USB0VBUS_46") (pintype "passive"))
    )
    (net (code "39") (name "Net-(U1A-PF0)") (class "Default")
      (node (ref "R14") (pin "2") (pinfunction "2_2") (pintype "passive"))
      (node (ref "U1") (pin "28") (pinfunction "PF0_28") (pintype "passive"))
    )
    (net (code "40") (name "Net-(U1B-OSC0)") (class "Default")
      (node (ref "C4") (pin "2") (pinfunction "2_2") (pintype "passive"))
      (node (ref "U1") (pin "40") (pinfunction "OSC0_40") (pintype "passive"))
      (node (ref "Y1") (pin "1") (pinfunction "1_1") (pintype "passive"))
    )
    (net (code "41") (name "Net-(U1B-OSC1)") (class "Default")
      (node (ref "C5") (pin "2") (pinfunction "2_2") (pintype "passive"))
      (node (ref "U1") (pin "41") (pinfunction "OSC1_41") (pintype "passive"))
      (node (ref "Y1") (pin "2") (pinfunction "2_2") (pintype "passive"))
    )
    (net (code "42") (name "unconnected-(A3-ASSOCIATE-Pad15)") (class "Default")
      (node (ref "A3") (pin "15") (pinfunction "ASSOCIATE_15") (pintype "passive"))
    )
    (net (code "43") (name "unconnected-(A3-CB-Pad20)") (class "Default")
      (node (ref "A3") (pin "20") (pinfunction "CB_20") (pintype "passive"))
    )
    (net (code "44") (name "unconnected-(A3-N{slash}A-Pad8)") (class "Default")
      (node (ref "A3") (pin "8") (pinfunction "N/A_8") (pintype "passive"))
    )
    (net (code "45") (name "unconnected-(A3-PWM0-Pad6)") (class "Default")
      (node (ref "A3") (pin "6") (pinfunction "PWM0_6") (pintype "passive"))
    )
    (net (code "46") (name "unconnected-(A3-PWM1-Pad7)") (class "Default")
      (node (ref "A3") (pin "7") (pinfunction "PWM1_7") (pintype "passive"))
    )
    (net (code "47") (name "unconnected-(A3-VREF-Pad14)") (class "Default")
      (node (ref "A3") (pin "14") (pinfunction "VREF_14") (pintype "passive"))
    )
    (net (code "48") (name "unconnected-(A3-~{CTS}-Pad12)") (class "Default")
      (node (ref "A3") (pin "12") (pinfunction "~{CTS}_12") (pintype "passive"))
    )
    (net (code "49") (name "unconnected-(A3-~{RTS}-Pad16)") (class "Default")
      (node (ref "A3") (pin "16") (pinfunction "~{RTS}_16") (pintype "passive"))
    )
    (net (code "50") (name "unconnected-(SW2-NC1-Pad1)") (class "Default")
      (node (ref "SW2") (pin "1") (pinfunction "NC1_1") (pintype "passive"))
    )
    (net (code "51") (name "unconnected-(SW2-NC2-Pad4)") (class "Default")
      (node (ref "SW2") (pin "4") (pinfunction "NC2_4") (pintype "passive"))
    )
    (net (code "52") (name "unconnected-(U1A-BF4-Pad5)") (class "Default")
      (node (ref "U1") (pin "5") (pinfunction "BF4_5") (pintype "passive"))
    )
    (net (code "53") (name "unconnected-(U1A-PA0{slash}U0Rx-Pad17)") (class "Default")
      (node (ref "U1") (pin "17") (pinfunction "PA0/U0Rx_17") (pintype "passive"))
    )
    (net (code "54") (name "unconnected-(U1A-PA1{slash}U0Tx-Pad18)") (class "Default")
      (node (ref "U1") (pin "18") (pinfunction "PA1/U0Tx_18") (pintype "passive"))
    )
    (net (code "55") (name "unconnected-(U1A-PB2{slash}I2C0SCL-Pad47)") (class "Default")
      (node (ref "U1") (pin "47") (pinfunction "PB2/I2C0SCL_47") (pintype "passive"))
    )
    (net (code "56") (name "unconnected-(U1A-PB3{slash}I2C0SDA-Pad48)") (class "Default")
      (node (ref "U1") (pin "48") (pinfunction "PB3/I2C0SDA_48") (pintype "passive"))
    )
    (net (code "57") (name "unconnected-(U1A-PC4-Pad16)") (class "Default")
      (node (ref "U1") (pin "16") (pinfunction "PC4_16") (pintype "passive"))
    )
    (net (code "58") (name "unconnected-(U1A-PC5-Pad15)") (class "Default")
      (node (ref "U1") (pin "15") (pinfunction "PC5_15") (pintype "passive"))
    )
    (net (code "59") (name "unconnected-(U1A-PC6-Pad14)") (class "Default")
      (node (ref "U1") (pin "14") (pinfunction "PC6_14") (pintype "passive"))
    )
    (net (code "60") (name "unconnected-(U1A-PC7-Pad13)") (class "Default")
      (node (ref "U1") (pin "13") (pinfunction "PC7_13") (pintype "passive"))
    )
    (net (code "61") (name "unconnected-(U1A-PD1-Pad62)") (class "Default")
      (node (ref "U1") (pin "62") (pinfunction "PD1_62") (pintype "passive"))
    )
    (net (code "62") (name "unconnected-(U1A-PD2-Pad63)") (class "Default")
      (node (ref "U1") (pin "63") (pinfunction "PD2_63") (pintype "passive"))
    )
    (net (code "63") (name "unconnected-(U1A-PD3-Pad64)") (class "Default")
      (node (ref "U1") (pin "64") (pinfunction "PD3_64") (pintype "passive"))
    )
    (net (code "64") (name "unconnected-(U1A-PD4-Pad43)") (class "Default")
      (node (ref "U1") (pin "43") (pinfunction "PD4_43") (pintype "passive"))
    )
    (net (code "65") (name "unconnected-(U1A-PD5-Pad44)") (class "Default")
      (node (ref "U1") (pin "44") (pinfunction "PD5_44") (pintype "passive"))
    )
    (net (code "66") (name "unconnected-(U1A-PD6-Pad53)") (class "Default")
      (node (ref "U1") (pin "53") (pinfunction "PD6_53") (pintype "passive"))
    )
    (net (code "67") (name "unconnected-(U1A-PD7-Pad10)") (class "Default")
      (node (ref "U1") (pin "10") (pinfunction "PD7_10") (pintype "passive"))
    )
    (net (code "68") (name "unconnected-(U1A-PE2-Pad7)") (class "Default")
      (node (ref "U1") (pin "7") (pinfunction "PE2_7") (pintype "passive"))
    )
    (net (code "69") (name "unconnected-(U1A-PE3-Pad6)") (class "Default")
      (node (ref "U1") (pin "6") (pinfunction "PE3_6") (pintype "passive"))
    )
    (net (code "70") (name "unconnected-(U1A-PF1-Pad29)") (class "Default")
      (node (ref "U1") (pin "29") (pinfunction "PF1_29") (pintype "passive"))
    )
    (net (code "71") (name "unconnected-(U1A-PF2-Pad30)") (class "Default")
      (node (ref "U1") (pin "30") (pinfunction "PF2_30") (pintype "passive"))
    )
    (net (code "72") (name "unconnected-(U1A-PF3-Pad31)") (class "Default")
      (node (ref "U1") (pin "31") (pinfunction "PF3_31") (pintype "passive"))
    )
    (net (code "73") (name "unconnected-(U1B-XOSC1-Pad36)") (class "Default")
      (node (ref "U1") (pin "36") (pinfunction "XOSC1_36") (pintype "passive"))
    )
    (net (code "74") (name "unconnected-(U1B-~{HIB}-Pad33)") (class "Default")
      (node (ref "U1") (pin "33") (pinfunction "~{HIB}_33") (pintype "passive"))
    )
    (net (code "75") (name "unconnected-(X1-Pad2)") (class "Default")
      (node (ref "X1") (pin "2") (pinfunction "2_2") (pintype "passive"))
    )
    (net (code "76") (name "unconnected-(X1-Pad4)") (class "Default")
      (node (ref "X1") (pin "4") (pinfunction "4_4") (pintype "passive"))
    )
    (net (code "77") (name "unconnected-(X2-NC-Pad1)") (class "Default")
      (node (ref "X2") (pin "1") (pinfunction "NC_1") (pintype "passive+no_connect"))
    )
    (net (code "78") (name "unconnected-(X2-NC-Pad8)") (class "Default")
      (node (ref "X2") (pin "8") (pinfunction "NC_8") (pintype "passive+no_connect"))
    )
    (net (code "79") (name "unconnected-(X3-Pad4)") (class "Default")
      (node (ref "X3") (pin "4") (pinfunction "4_4") (pintype "passive"))
    )
    (net (code "80") (name "unconnected-(X3-Pad5)") (class "Default")
      (node (ref "X3") (pin "5") (pinfunction "5_5") (pintype "passive"))
    )
    (net (code "81") (name "unconnected-(X3-Pad8)") (class "Default")
      (node (ref "X3") (pin "8") (pinfunction "8_8") (pintype "passive"))
    )
  )
)
